# Electrovalvulas.net
KiCad netlist of a schematic drawn in Altium Designer
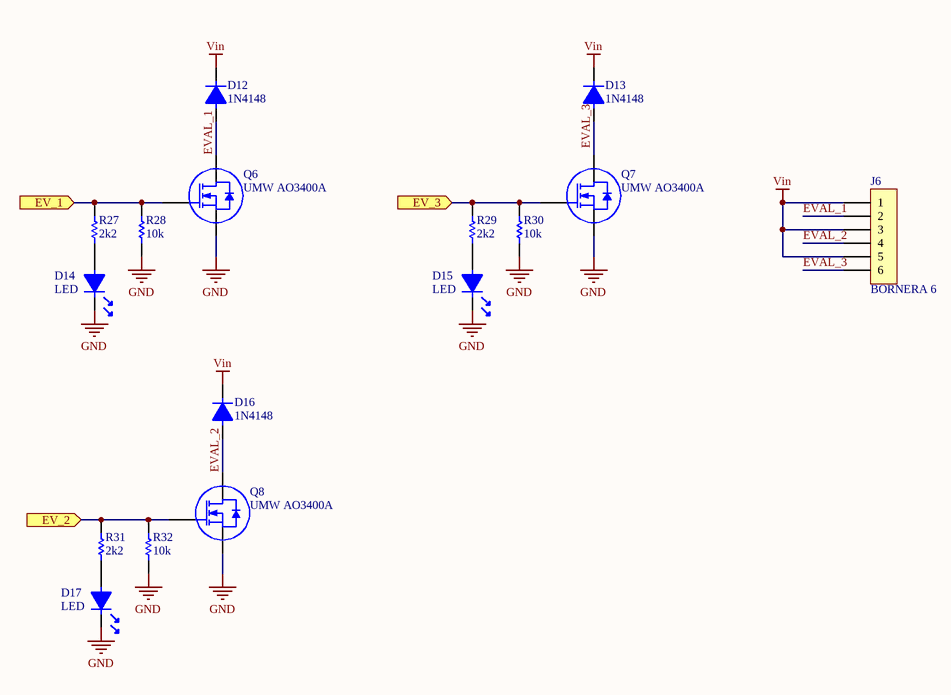
[diagram p0: Electrovalvulas.SchDoc]

(export (version "E")
  (design (tool "Eeschema 10.0.6"))
  (components
    (comp (ref "D12") (value "1N4148") (footprint "1206K") (libsource (lib "LIBPIOIX") (part "DIODO")))
    (comp (ref "D13") (value "1N4148") (footprint "1206K") (libsource (lib "LIBPIOIX") (part "DIODO")))
    (comp (ref "D14") (value "LED") (footprint "LED0805") (libsource (lib "LIBPIOIX") (part "LED")))
    (comp (ref "D15") (value "LED") (footprint "LED0805") (libsource (lib "LIBPIOIX") (part "LED")))
    (comp (ref "D16") (value "1N4148") (footprint "1206K") (libsource (lib "LIBPIOIX") (part "DIODO")))
    (comp (ref "D17") (value "LED") (footprint "LED0805") (libsource (lib "LIBPIOIX") (part "LED")))
    (comp (ref "J6")
      (value "BORNERA 6")
      (footprint "BORNERA6")
      (libsource (lib "LIBPIOIX") (part "BORNERA 6"))
    )
    (comp (ref "Q6") (value "UMW AO3400A") (footprint "SOT23") (libsource (lib "LIBPIOIX") (part "MOSFET N")))
    (comp (ref "Q7") (value "UMW AO3400A") (footprint "SOT23") (libsource (lib "LIBPIOIX") (part "MOSFET N")))
    (comp (ref "Q8") (value "UMW AO3400A") (footprint "SOT23") (libsource (lib "LIBPIOIX") (part "MOSFET N")))
    (comp (ref "R27") (value "2k2") (footprint "0805") (libsource (lib "LIBPIOIX") (part "RES")))
    (comp (ref "R28") (value "10k") (footprint "0805") (libsource (lib "LIBPIOIX") (part "RES")))
    (comp (ref "R29") (value "2k2") (footprint "0805") (libsource (lib "LIBPIOIX") (part "RES")))
    (comp (ref "R30") (value "10k") (footprint "0805") (libsource (lib "LIBPIOIX") (part "RES")))
    (comp (ref "R31") (value "2k2") (footprint "0805") (libsource (lib "LIBPIOIX") (part "RES")))
    (comp (ref "R32") (value "10k") (footprint "0805") (libsource (lib "LIBPIOIX") (part "RES")))
  )
  (nets
    (net (code "1") (name "/EVAL_1") (class "Default")
      (node (ref "D12") (pin "1") (pinfunction "1_1") (pintype "passive"))
      (node (ref "J6") (pin "2") (pinfunction "2_2") (pintype "passive"))
      (node (ref "Q6") (pin "2") (pinfunction "D_2") (pintype "passive"))
    )
    (net (code "2") (name "/EVAL_2") (class "Default")
      (node (ref "D16") (pin "1") (pinfunction "1_1") (pintype "passive"))
      (node (ref "J6") (pin "4") (pinfunction "4_4") (pintype "passive"))
      (node (ref "Q8") (pin "2") (pinfunction "D_2") (pintype "passive"))
    )
    (net (code "3") (name "/EVAL_3") (class "Default")
      (node (ref "D13") (pin "1") (pinfunction "1_1") (pintype "passive"))
      (node (ref "J6") (pin "6") (pinfunction "6_6") (pintype "passive"))
      (node (ref "Q7") (pin "2") (pinfunction "D_2") (pintype "passive"))
    )
    (net (code "4") (name "/EV_1") (class "Default")
      (node (ref "Q6") (pin "1") (pinfunction "G_1") (pintype "passive"))
      (node (ref "R27") (pin "2") (pinfunction "2_2") (pintype "passive"))
      (node (ref "R28") (pin "2") (pinfunction "2_2") (pintype "passive"))
    )
    (net (code "5") (name "/EV_2") (class "Default")
      (node (ref "Q8") (pin "1") (pinfunction "G_1") (pintype "passive"))
      (node (ref "R31") (pin "2") (pinfunction "2_2") (pintype "passive"))
      (node (ref "R32") (pin "2") (pinfunction "2_2") (pintype "passive"))
    )
    (net (code "6") (name "/EV_3") (class "Default")
      (node (ref "Q7") (pin "1") (pinfunction "G_1") (pintype "passive"))
      (node (ref "R29") (pin "2") (pinfunction "2_2") (pintype "passive"))
      (node (ref "R30") (pin "2") (pinfunction "2_2") (pintype "passive"))
    )
    (net (code "7") (name "GND") (class "Default")
      (node (ref "D14") (pin "2") (pinfunction "2_2") (pintype "passive"))
      (node (ref "D15") (pin "2") (pinfunction "2_2") (pintype "passive"))
      (node (ref "D17") (pin "2") (pinfunction "2_2") (pintype "passive"))
      (node (ref "Q6") (pin "3") (pinfunction "S_3") (pintype "passive"))
      (node (ref "Q7") (pin "3") (pinfunction "S_3") (pintype "passive"))
      (node (ref "Q8") (pin "3") (pinfunction "S_3") (pintype "passive"))
      (node (ref "R28") (pin "1") (pinfunction "1_1") (pintype "passive"))
      (node (ref "R30") (pin "1") (pinfunction "1_1") (pintype "passive"))
      (node (ref "R32") (pin "1") (pinfunction "1_1") (pintype "passive"))
    )
    (net (code "8") (name "Net-(D14-Pad1)") (class "Default")
      (node (ref "D14") (pin "1") (pinfunction "1_1") (pintype "passive"))
      (node (ref "R27") (pin "1") (pinfunction "1_1") (pintype "passive"))
    )
    (net (code "9") (name "Net-(D15-Pad1)") (class "Default")
      (node (ref "D15") (pin "1") (pinfunction "1_1") (pintype "passive"))
      (node (ref "R29") (pin "1") (pinfunction "1_1") (pintype "passive"))
    )
    (net (code "10") (name "Net-(D17-Pad1)") (class "Default")
      (node (ref "D17") (pin "1") (pinfunction "1_1") (pintype "passive"))
      (node (ref "R31") (pin "1") (pinfunction "1_1") (pintype "passive"))
    )
    (net (code "11") (name "Vin") (class "Default")
      (node (ref "D12") (pin "2") (pinfunction "2_2") (pintype "passive"))
      (node (ref "D13") (pin "2") (pinfunction "2_2") (pintype "passive"))
      (node (ref "D16") (pin "2") (pinfunction "2_2") (pintype "passive"))
      (node (ref "J6") (pin "1") (pinfunction "1_1") (pintype "passive"))
      (node (ref "J6") (pin "3") (pinfunction "3_3") (pintype "passive"))
      (node (ref "J6") (pin "5") (pinfunction "5_5") (pintype "passive"))
    )
  )
)
